# Sheet.net
KiCad netlist of a schematic drawn in Altium Designer
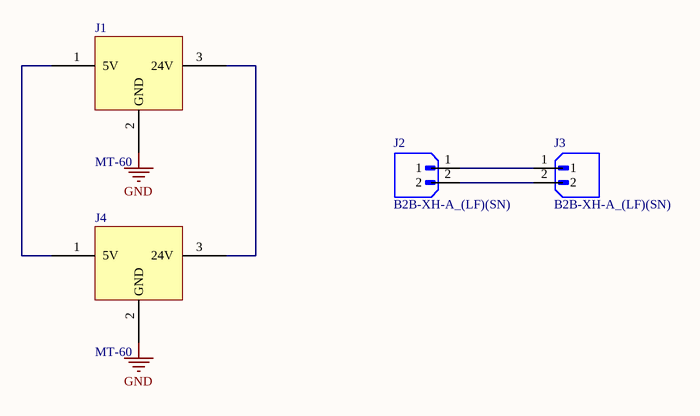
[diagram p0: Sheet.SchDoc]

(export (version "E")
  (design (tool "Eeschema 10.0.6"))
  (components
    (comp (ref "J1")
      (value "MT-60")
      (footprint "MT-60")
      (fields (field (name "LCSC PART #") "C99176"))
      (libsource (lib "Mt-60") (part "MT-60"))
    )
    (comp (ref "J2")
      (value "B2B-XH-A_(LF)(SN)")
      (footprint "JST_B2B-XH-A_(LF)(SN)")
      (description "Connector Header Through Hole 2 position 0.098 (2.50mm)")
      (fields (field (name "MF") "JST Sales") (field (name "MP") "B2B-XH-A (LF)(SN)"))
      (libsource (lib "B2B-XH-A__LF__SN_") (part "B2B-XH-A_(LF)(SN)"))
    )
    (comp (ref "J3")
      (value "B2B-XH-A_(LF)(SN)")
      (footprint "JST_B2B-XH-A_(LF)(SN)")
      (description "Connector Header Through Hole 2 position 0.098 (2.50mm)")
      (fields (field (name "MF") "JST Sales") (field (name "MP") "B2B-XH-A (LF)(SN)"))
      (libsource (lib "") (part "B2B-XH-A_(LF)(SN)_1"))
    )
    (comp (ref "J4")
      (value "MT-60")
      (footprint "MT-60")
      (fields (field (name "LCSC PART #") "C99176"))
      (libsource (lib "Mt-60") (part "MT-60"))
    )
  )
  (nets
    (net (code "1") (name "GND") (class "Default")
      (node (ref "J1") (pin "2") (pinfunction "GND_2") (pintype "passive"))
      (node (ref "J4") (pin "2") (pinfunction "GND_2") (pintype "passive"))
    )
    (net (code "2") (name "Net-(J1-5V)") (class "Default")
      (node (ref "J1") (pin "1") (pinfunction "5V_1") (pintype "passive"))
      (node (ref "J4") (pin "1") (pinfunction "5V_1") (pintype "passive"))
    )
    (net (code "3") (name "Net-(J1-24V)") (class "Default")
      (node (ref "J1") (pin "3") (pinfunction "24V_3") (pintype "passive"))
      (node (ref "J4") (pin "3") (pinfunction "24V_3") (pintype "passive"))
    )
    (net (code "4") (name "Net-(J2-Pad1)") (class "Default")
      (node (ref "J2") (pin "1") (pinfunction "1_1") (pintype "passive"))
      (node (ref "J3") (pin "1") (pinfunction "1_1") (pintype "passive"))
    )
    (net (code "5") (name "Net-(J2-Pad2)") (class "Default")
      (node (ref "J2") (pin "2") (pinfunction "2_2") (pintype "passive"))
      (node (ref "J3") (pin "2") (pinfunction "2_2") (pintype "passive"))
    )
  )
)
